# SallenKeyLowPass.net
KiCad netlist of a schematic drawn in Altium Designer
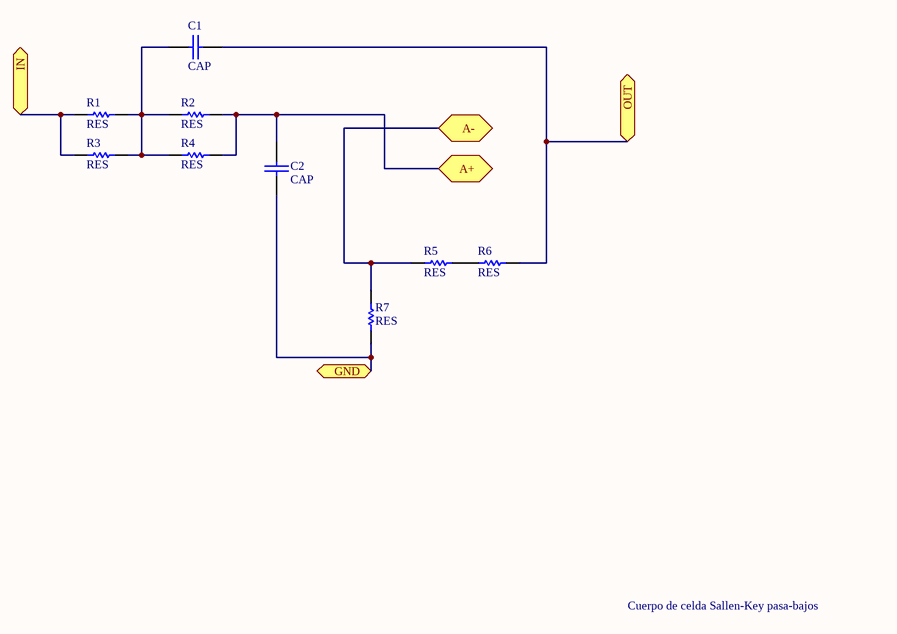
[diagram p0: SallenKeyLowPass.SchDoc]

(export (version "E")
  (design (tool "Eeschema 10.0.6"))
  (components
    (comp (ref "C1") (value "CAP") (footprint "CAP100") (libsource (lib "LIBEBAL") (part "CAP")))
    (comp (ref "C2") (value "CAP") (footprint "CAP100") (libsource (lib "LIBEBAL") (part "CAP")))
    (comp (ref "R1") (value "RES") (footprint "RES300") (libsource (lib "LIBEBAL") (part "RES")))
    (comp (ref "R2") (value "RES") (footprint "RES300") (libsource (lib "LIBEBAL") (part "RES")))
    (comp (ref "R3") (value "RES") (footprint "RES300") (libsource (lib "LIBEBAL") (part "RES")))
    (comp (ref "R4") (value "RES") (footprint "RES300") (libsource (lib "LIBEBAL") (part "RES")))
    (comp (ref "R5") (value "RES") (footprint "RES300") (libsource (lib "LIBEBAL") (part "RES")))
    (comp (ref "R6") (value "RES") (footprint "RES300") (libsource (lib "LIBEBAL") (part "RES")))
    (comp (ref "R7") (value "RES") (footprint "RES300") (libsource (lib "LIBEBAL") (part "RES")))
  )
  (nets
    (net (code "1") (name "/A+") (class "Default")
      (node (ref "C2") (pin "1") (pinfunction "1_1") (pintype "passive"))
      (node (ref "R2") (pin "2") (pinfunction "2_2") (pintype "passive"))
      (node (ref "R4") (pin "2") (pinfunction "2_2") (pintype "passive"))
    )
    (net (code "2") (name "/A-") (class "Default")
      (node (ref "R5") (pin "2") (pinfunction "2_2") (pintype "passive"))
      (node (ref "R7") (pin "2") (pinfunction "2_2") (pintype "passive"))
    )
    (net (code "3") (name "/GND") (class "Default")
      (node (ref "C2") (pin "2") (pinfunction "2_2") (pintype "passive"))
      (node (ref "R7") (pin "1") (pinfunction "1_1") (pintype "passive"))
    )
    (net (code "4") (name "/IN") (class "Default")
      (node (ref "R1") (pin "1") (pinfunction "1_1") (pintype "passive"))
      (node (ref "R3") (pin "1") (pinfunction "1_1") (pintype "passive"))
    )
    (net (code "5") (name "/OUT") (class "Default")
      (node (ref "C1") (pin "2") (pinfunction "2_2") (pintype "passive"))
      (node (ref "R6") (pin "1") (pinfunction "1_1") (pintype "passive"))
    )
    (net (code "6") (name "Net-(C1-Pad1)") (class "Default")
      (node (ref "C1") (pin "1") (pinfunction "1_1") (pintype "passive"))
      (node (ref "R1") (pin "2") (pinfunction "2_2") (pintype "passive"))
      (node (ref "R2") (pin "1") (pinfunction "1_1") (pintype "passive"))
      (node (ref "R3") (pin "2") (pinfunction "2_2") (pintype "passive"))
      (node (ref "R4") (pin "1") (pinfunction "1_1") (pintype "passive"))
    )
    (net (code "7") (name "Net-(R5-Pad1)") (class "Default")
      (node (ref "R5") (pin "1") (pinfunction "1_1") (pintype "passive"))
      (node (ref "R6") (pin "2") (pinfunction "2_2") (pintype "passive"))
    )
  )
)
